# power.net
KiCad netlist of a schematic drawn in Altium Designer
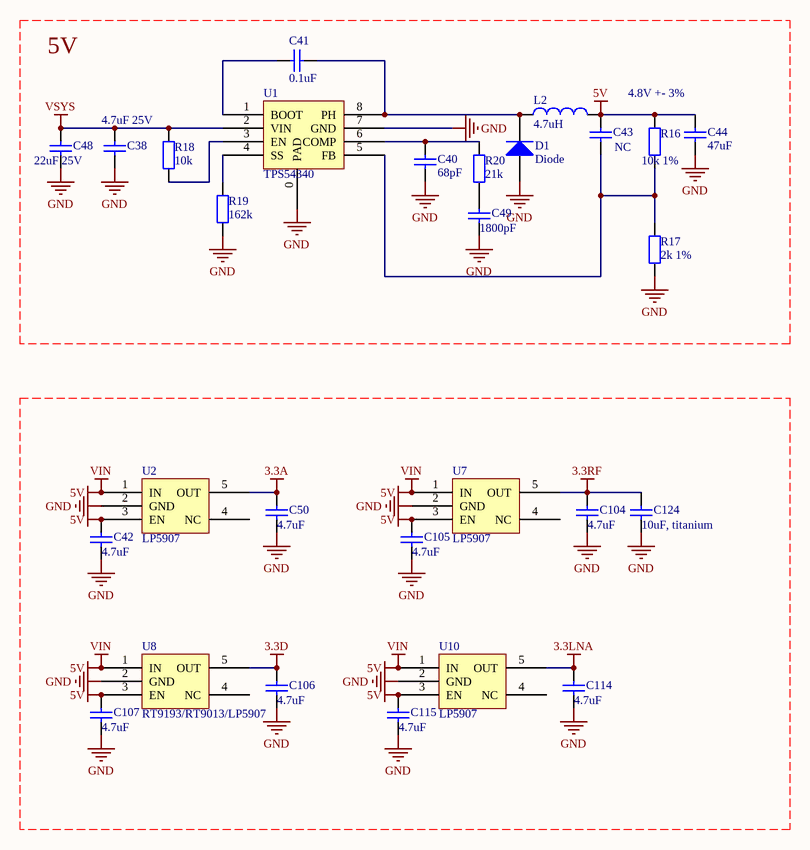
[diagram p0: power.SchDoc]

(export (version "E")
  (design (tool "Eeschema 10.0.6"))
  (components
    (comp (ref "C38")
      (value "4.7uF 25V")
      (footprint "0805")
      (description "Capacitor")
      (fields (field (name "Comment") "Cap") (field (name "PUBLISHER") "Altium Limited"))
      (libsource (lib "RTC6705") (part "Cap"))
    )
    (comp (ref "C40")
      (value "68pF")
      (footprint "0402")
      (description "Capacitor")
      (fields (field (name "Comment") "Cap") (field (name "PUBLISHER") "Altium Limited"))
      (libsource (lib "RTC6705") (part "Cap"))
    )
    (comp (ref "C41")
      (value "0.1uF")
      (footprint "0402")
      (description "Capacitor")
      (fields (field (name "Comment") "Cap") (field (name "PUBLISHER") "Altium Limited"))
      (libsource (lib "RTC6705") (part "Cap"))
    )
    (comp (ref "C42")
      (value "4.7uF")
      (footprint "0603")
      (description "Capacitor")
      (fields (field (name "PUBLISHER") "Altium Limited"))
      (libsource (lib "RTC6705") (part "Cap"))
    )
    (comp (ref "C43")
      (value "NC")
      (footprint "0402")
      (description "Capacitor")
      (fields (field (name "PUBLISHER") "Altium Limited"))
      (libsource (lib "RTC6705") (part "Cap"))
    )
    (comp (ref "C44")
      (value "47uF")
      (footprint "1210")
      (description "Capacitor")
      (fields (field (name "Comment") "Cap") (field (name "PUBLISHER") "Altium Limited"))
      (libsource (lib "RTC6705") (part "Cap"))
    )
    (comp (ref "C48")
      (value "22uF 25V")
      (footprint "1210")
      (description "Capacitor")
      (fields (field (name "Comment") "Cap") (field (name "PUBLISHER") "Altium Limited"))
      (libsource (lib "RTC6705") (part "Cap"))
    )
    (comp (ref "C49")
      (value "1800pF")
      (footprint "0402")
      (description "Capacitor")
      (fields (field (name "Comment") "Cap") (field (name "PUBLISHER") "Altium Limited"))
      (libsource (lib "RTC6705") (part "Cap"))
    )
    (comp (ref "C50")
      (value "4.7uF")
      (footprint "0603")
      (description "Capacitor")
      (fields (field (name "PUBLISHER") "Altium Limited"))
      (libsource (lib "RTC6705") (part "Cap"))
    )
    (comp (ref "C104")
      (value "4.7uF")
      (footprint "0603")
      (description "Capacitor")
      (fields (field (name "PUBLISHER") "Altium Limited"))
      (libsource (lib "RTC6705") (part "Cap"))
    )
    (comp (ref "C105")
      (value "4.7uF")
      (footprint "0603")
      (description "Capacitor")
      (fields (field (name "PUBLISHER") "Altium Limited"))
      (libsource (lib "RTC6705") (part "Cap"))
    )
    (comp (ref "C106")
      (value "4.7uF")
      (footprint "0603")
      (description "Capacitor")
      (fields (field (name "PUBLISHER") "Altium Limited"))
      (libsource (lib "RTC6705") (part "Cap"))
    )
    (comp (ref "C107")
      (value "4.7uF")
      (footprint "0603")
      (description "Capacitor")
      (fields (field (name "PUBLISHER") "Altium Limited"))
      (libsource (lib "RTC6705") (part "Cap"))
    )
    (comp (ref "C114")
      (value "4.7uF")
      (footprint "0603")
      (description "Capacitor")
      (fields (field (name "PUBLISHER") "Altium Limited"))
      (libsource (lib "RTC6705") (part "Cap"))
    )
    (comp (ref "C115")
      (value "4.7uF")
      (footprint "0603")
      (description "Capacitor")
      (fields (field (name "PUBLISHER") "Altium Limited"))
      (libsource (lib "RTC6705") (part "Cap"))
    )
    (comp (ref "C124")
      (value "10uF, titanium")
      (footprint "0805")
      (description "Capacitor")
      (fields (field (name "PUBLISHER") "Altium Limited"))
      (libsource (lib "RTC6705") (part "Cap"))
    )
    (comp (ref "D1")
      (value "Diode")
      (footprint "LC-SMB(DO-214AA)_S5")
      (description "Default Diode")
      (fields (field (name "PUBLISHER") "Altium Limited"))
      (libsource (lib "Miscellaneous Devices") (part "Diode"))
    )
    (comp (ref "L2")
      (value "4.7uH")
      (footprint "L7022")
      (description "Inductor")
      (fields (field (name "PUBLISHER") "Altium Limited"))
      (libsource (lib "Miscellaneous Devices") (part "Inductor"))
    )
    (comp (ref "R16")
      (value "10k 1%")
      (footprint "0402")
      (description "Resistor")
      (fields (field (name "Comment") "Res2") (field (name "PUBLISHER") "Altium Limited"))
      (libsource (lib "RTC6705") (part "Res2"))
    )
    (comp (ref "R17")
      (value "2k 1%")
      (footprint "0402")
      (description "Resistor")
      (fields (field (name "Comment") "Res2") (field (name "PUBLISHER") "Altium Limited"))
      (libsource (lib "RTC6705") (part "Res2"))
    )
    (comp (ref "R18")
      (value "10k")
      (footprint "0402")
      (description "Resistor")
      (fields (field (name "Comment") "Res2") (field (name "PUBLISHER") "Altium Limited"))
      (libsource (lib "RTC6705") (part "Res2"))
    )
    (comp (ref "R19")
      (value "162k")
      (footprint "0402")
      (description "Resistor")
      (fields (field (name "Comment") "Res2") (field (name "PUBLISHER") "Altium Limited"))
      (libsource (lib "RTC6705") (part "Res2"))
    )
    (comp (ref "R20")
      (value "21k")
      (footprint "0402")
      (description "Resistor")
      (fields (field (name "Comment") "Res2") (field (name "PUBLISHER") "Altium Limited"))
      (libsource (lib "RTC6705") (part "Res2"))
    )
    (comp (ref "U1") (value "TPS54340") (footprint "D8-Pad") (libsource (lib "sch") (part "TPS54340")))
    (comp (ref "U2") (value "LP5907") (footprint "SOT23-5") (libsource (lib "RTC6705") (part "LP5907")))
    (comp (ref "U7") (value "LP5907") (footprint "SOT23-5") (libsource (lib "RTC6705") (part "LP5907")))
    (comp (ref "U8")
      (value "RT9193/RT9013/LP5907")
      (footprint "SOT23-5")
      (libsource (lib "RTC6705") (part "LP5907"))
    )
    (comp (ref "U10") (value "LP5907") (footprint "SOT23-5") (libsource (lib "RTC6705") (part "LP5907")))
  )
  (nets
    (net (code "1") (name "3.3A") (class "Default")
      (node (ref "C50") (pin "2") (pinfunction "2_2") (pintype "passive"))
      (node (ref "U2") (pin "5") (pinfunction "OUT_5") (pintype "passive"))
    )
    (net (code "2") (name "3.3D") (class "Default")
      (node (ref "C106") (pin "2") (pinfunction "2_2") (pintype "passive"))
      (node (ref "U8") (pin "5") (pinfunction "OUT_5") (pintype "passive"))
    )
    (net (code "3") (name "3.3LNA") (class "Default")
      (node (ref "C114") (pin "2") (pinfunction "2_2") (pintype "passive"))
      (node (ref "U10") (pin "5") (pinfunction "OUT_5") (pintype "passive"))
    )
    (net (code "4") (name "3.3RF") (class "Default")
      (node (ref "C104") (pin "2") (pinfunction "2_2") (pintype "passive"))
      (node (ref "C124") (pin "2") (pinfunction "2_2") (pintype "passive"))
      (node (ref "U7") (pin "5") (pinfunction "OUT_5") (pintype "passive"))
    )
    (net (code "5") (name "5V") (class "Default")
      (node (ref "C105") (pin "2") (pinfunction "2_2") (pintype "passive"))
      (node (ref "C107") (pin "2") (pinfunction "2_2") (pintype "passive"))
      (node (ref "C115") (pin "2") (pinfunction "2_2") (pintype "passive"))
      (node (ref "C42") (pin "2") (pinfunction "2_2") (pintype "passive"))
      (node (ref "C43") (pin "1") (pinfunction "1_1") (pintype "passive"))
      (node (ref "C44") (pin "1") (pinfunction "1_1") (pintype "passive"))
      (node (ref "L2") (pin "2") (pinfunction "2_2") (pintype "passive"))
      (node (ref "R16") (pin "1") (pinfunction "1_1") (pintype "passive"))
      (node (ref "U10") (pin "1") (pinfunction "IN_1") (pintype "passive"))
      (node (ref "U10") (pin "3") (pinfunction "EN_3") (pintype "passive"))
      (node (ref "U2") (pin "1") (pinfunction "IN_1") (pintype "passive"))
      (node (ref "U2") (pin "3") (pinfunction "EN_3") (pintype "passive"))
      (node (ref "U7") (pin "1") (pinfunction "IN_1") (pintype "passive"))
      (node (ref "U7") (pin "3") (pinfunction "EN_3") (pintype "passive"))
      (node (ref "U8") (pin "1") (pinfunction "IN_1") (pintype "passive"))
      (node (ref "U8") (pin "3") (pinfunction "EN_3") (pintype "passive"))
    )
    (net (code "6") (name "GND") (class "Default")
      (node (ref "C104") (pin "1") (pinfunction "1_1") (pintype "passive"))
      (node (ref "C105") (pin "1") (pinfunction "1_1") (pintype "passive"))
      (node (ref "C106") (pin "1") (pinfunction "1_1") (pintype "passive"))
      (node (ref "C107") (pin "1") (pinfunction "1_1") (pintype "passive"))
      (node (ref "C114") (pin "1") (pinfunction "1_1") (pintype "passive"))
      (node (ref "C115") (pin "1") (pinfunction "1_1") (pintype "passive"))
      (node (ref "C124") (pin "1") (pinfunction "1_1") (pintype "passive"))
      (node (ref "C38") (pin "2") (pinfunction "2_2") (pintype "passive"))
      (node (ref "C40") (pin "2") (pinfunction "2_2") (pintype "passive"))
      (node (ref "C42") (pin "1") (pinfunction "1_1") (pintype "passive"))
      (node (ref "C44") (pin "2") (pinfunction "2_2") (pintype "passive"))
      (node (ref "C48") (pin "2") (pinfunction "2_2") (pintype "passive"))
      (node (ref "C49") (pin "2") (pinfunction "2_2") (pintype "passive"))
      (node (ref "C50") (pin "1") (pinfunction "1_1") (pintype "passive"))
      (node (ref "D1") (pin "1") (pinfunction "A_1") (pintype "passive"))
      (node (ref "R17") (pin "2") (pinfunction "2_2") (pintype "passive"))
      (node (ref "R19") (pin "2") (pinfunction "2_2") (pintype "passive"))
      (node (ref "U1") (pin "0") (pinfunction "PAD_0") (pintype "passive"))
      (node (ref "U1") (pin "7") (pinfunction "GND_7") (pintype "passive"))
      (node (ref "U10") (pin "2") (pinfunction "GND_2") (pintype "passive"))
      (node (ref "U2") (pin "2") (pinfunction "GND_2") (pintype "passive"))
      (node (ref "U7") (pin "2") (pinfunction "GND_2") (pintype "passive"))
      (node (ref "U8") (pin "2") (pinfunction "GND_2") (pintype "passive"))
    )
    (net (code "7") (name "Net-(C49-Pad1)") (class "Default")
      (node (ref "C49") (pin "1") (pinfunction "1_1") (pintype "passive"))
      (node (ref "R20") (pin "2") (pinfunction "2_2") (pintype "passive"))
    )
    (net (code "8") (name "Net-(D1-K)") (class "Default")
      (node (ref "C41") (pin "1") (pinfunction "1_1") (pintype "passive"))
      (node (ref "D1") (pin "2") (pinfunction "K_2") (pintype "passive"))
      (node (ref "L2") (pin "1") (pinfunction "1_1") (pintype "passive"))
      (node (ref "U1") (pin "8") (pinfunction "PH_8") (pintype "passive"))
    )
    (net (code "9") (name "Net-(U1-BOOT)") (class "Default")
      (node (ref "C41") (pin "2") (pinfunction "2_2") (pintype "passive"))
      (node (ref "U1") (pin "1") (pinfunction "BOOT_1") (pintype "passive"))
    )
    (net (code "10") (name "Net-(U1-COMP)") (class "Default")
      (node (ref "C40") (pin "1") (pinfunction "1_1") (pintype "passive"))
      (node (ref "R20") (pin "1") (pinfunction "1_1") (pintype "passive"))
      (node (ref "U1") (pin "6") (pinfunction "COMP_6") (pintype "passive"))
    )
    (net (code "11") (name "Net-(U1-EN)") (class "Default")
      (node (ref "R18") (pin "2") (pinfunction "2_2") (pintype "passive"))
      (node (ref "U1") (pin "3") (pinfunction "EN_3") (pintype "passive"))
    )
    (net (code "12") (name "Net-(U1-FB)") (class "Default")
      (node (ref "C43") (pin "2") (pinfunction "2_2") (pintype "passive"))
      (node (ref "R16") (pin "2") (pinfunction "2_2") (pintype "passive"))
      (node (ref "R17") (pin "1") (pinfunction "1_1") (pintype "passive"))
      (node (ref "U1") (pin "5") (pinfunction "FB_5") (pintype "passive"))
    )
    (net (code "13") (name "Net-(U1-SS)") (class "Default")
      (node (ref "R19") (pin "1") (pinfunction "1_1") (pintype "passive"))
      (node (ref "U1") (pin "4") (pinfunction "SS_4") (pintype "passive"))
    )
    (net (code "14") (name "VSYS") (class "Default")
      (node (ref "C38") (pin "1") (pinfunction "1_1") (pintype "passive"))
      (node (ref "C48") (pin "1") (pinfunction "1_1") (pintype "passive"))
      (node (ref "R18") (pin "1") (pinfunction "1_1") (pintype "passive"))
      (node (ref "U1") (pin "2") (pinfunction "VIN_2") (pintype "passive"))
    )
    (net (code "15") (name "unconnected-(U2-NC-Pad4)") (class "Default")
      (node (ref "U2") (pin "4") (pinfunction "NC_4") (pintype "passive"))
    )
    (net (code "16") (name "unconnected-(U7-NC-Pad4)") (class "Default")
      (node (ref "U7") (pin "4") (pinfunction "NC_4") (pintype "passive"))
    )
    (net (code "17") (name "unconnected-(U8-NC-Pad4)") (class "Default")
      (node (ref "U8") (pin "4") (pinfunction "NC_4") (pintype "passive"))
    )
    (net (code "18") (name "unconnected-(U10-NC-Pad4)") (class "Default")
      (node (ref "U10") (pin "4") (pinfunction "NC_4") (pintype "passive"))
    )
  )
)
